# HW2_Schematic.net
KiCad netlist of a schematic drawn in EAGLE
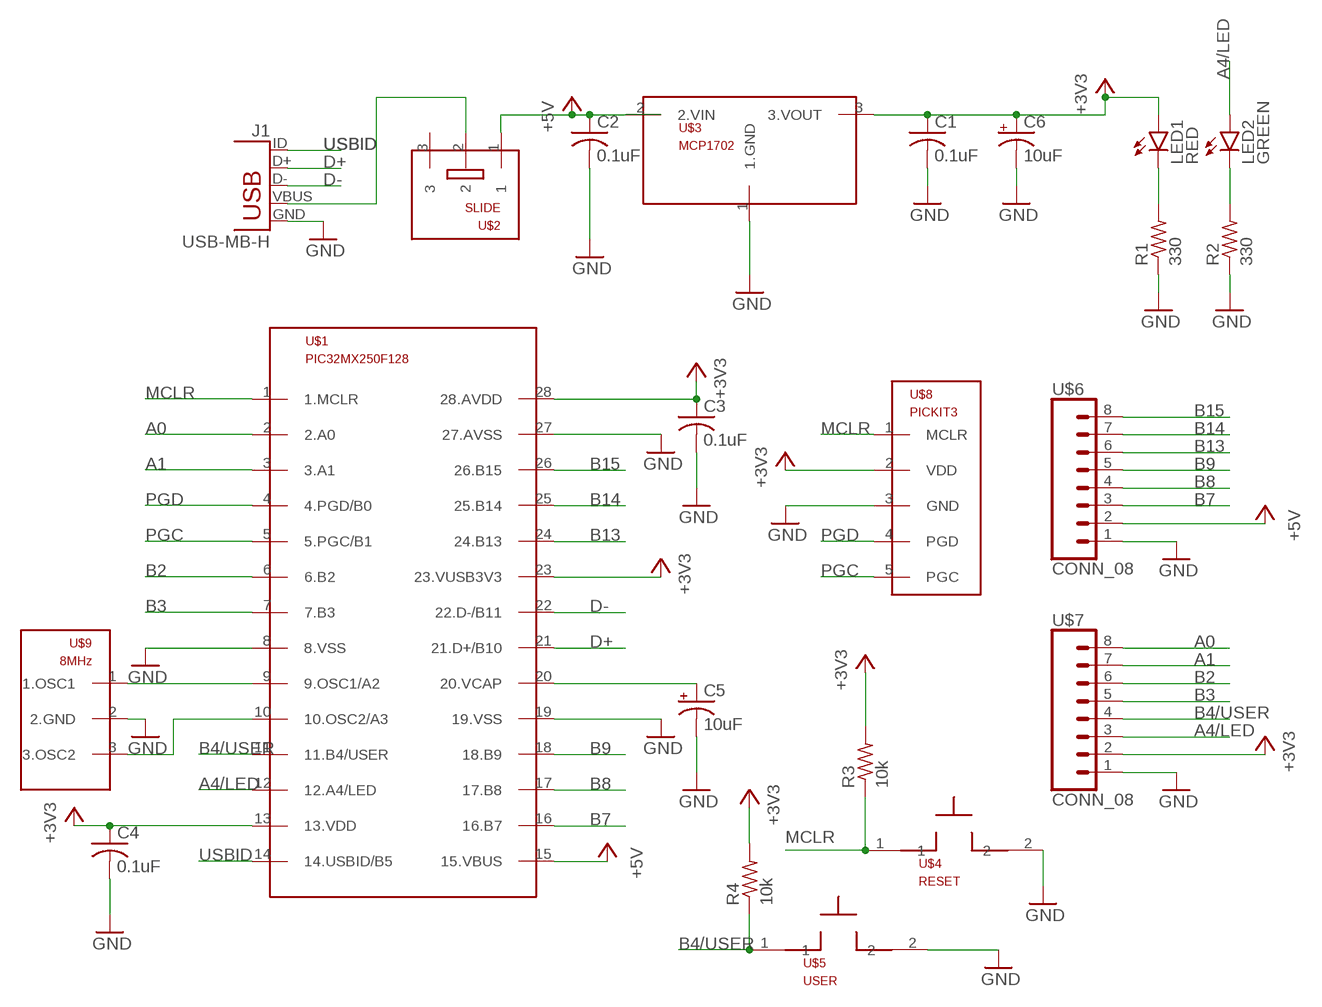
[diagram p0: schematic, sheet 1]

(export (version "E")
  (design (tool "Eeschema 10.0.6"))
  (components
    (comp (ref "C1")
      (value "0.1uF")
      (footprint "eagle-import:C025-025X050")
      (libsource (lib "eagle-import") (part "C-US025-025X050"))
    )
    (comp (ref "C2")
      (value "0.1uF")
      (footprint "eagle-import:C025-025X050")
      (libsource (lib "eagle-import") (part "C-US025-025X050"))
    )
    (comp (ref "C3")
      (value "0.1uF")
      (footprint "eagle-import:C025-025X050")
      (libsource (lib "eagle-import") (part "C-US025-025X050"))
    )
    (comp (ref "C4")
      (value "0.1uF")
      (footprint "eagle-import:C025-025X050")
      (libsource (lib "eagle-import") (part "C-US025-025X050"))
    )
    (comp (ref "C5")
      (value "10uF")
      (footprint "eagle-import:B45181B")
      (libsource (lib "eagle-import") (part "CPOL-USB45181B"))
    )
    (comp (ref "C6")
      (value "10uF")
      (footprint "eagle-import:B45181B")
      (libsource (lib "eagle-import") (part "CPOL-USB45181B"))
    )
    (comp (ref "J1")
      (value "USB-MB-H")
      (footprint "eagle-import:USB-MB-H")
      (libsource (lib "eagle-import") (part "USB-MB-H"))
    )
    (comp (ref "LED1")
      (value "RED")
      (footprint "eagle-import:LED3MM")
      (libsource (lib "eagle-import") (part "LED3MM"))
    )
    (comp (ref "LED2")
      (value "GREEN")
      (footprint "eagle-import:LED3MM")
      (libsource (lib "eagle-import") (part "LED3MM"))
    )
    (comp (ref "R1")
      (value "330")
      (footprint "eagle-import:0207_10")
      (libsource (lib "eagle-import") (part "R-US_0207/10"))
    )
    (comp (ref "R2")
      (value "330")
      (footprint "eagle-import:0207_10")
      (libsource (lib "eagle-import") (part "R-US_0207/10"))
    )
    (comp (ref "R3")
      (value "10k")
      (footprint "eagle-import:0207_10")
      (libsource (lib "eagle-import") (part "R-US_0207/10"))
    )
    (comp (ref "R4")
      (value "10k")
      (footprint "eagle-import:0207_10")
      (libsource (lib "eagle-import") (part "R-US_0207/10"))
    )
    (comp (ref "U$1")
      (value "PIC32MX250F128")
      (footprint "eagle-import:DIL28-3")
      (libsource (lib "eagle-import") (part "PIC32MX250F128"))
    )
    (comp (ref "U$2")
      (value "SLIDE")
      (footprint "eagle-import:SLIDE")
      (libsource (lib "eagle-import") (part "SLIDE"))
    )
    (comp (ref "U$3")
      (value "MCP1702")
      (footprint "eagle-import:TO92")
      (libsource (lib "eagle-import") (part "MCP1702"))
    )
    (comp (ref "U$4")
      (value "RESET")
      (footprint "eagle-import:PB")
      (libsource (lib "eagle-import") (part "PB"))
    )
    (comp (ref "U$5")
      (value "USER")
      (footprint "eagle-import:PB")
      (libsource (lib "eagle-import") (part "PB"))
    )
    (comp (ref "U$6")
      (value "CONN_08")
      (footprint "eagle-import:1X08")
      (libsource (lib "eagle-import") (part "CONN_08"))
    )
    (comp (ref "U$7")
      (value "CONN_08")
      (footprint "eagle-import:1X08")
      (libsource (lib "eagle-import") (part "CONN_08"))
    )
    (comp (ref "U$8")
      (value "PICKIT3")
      (footprint "eagle-import:1X05")
      (libsource (lib "eagle-import") (part "PICKIT3"))
    )
    (comp (ref "U$9")
      (value "8MHz")
      (footprint "eagle-import:OSC")
      (libsource (lib "eagle-import") (part "OSC"))
    )
  )
  (nets
    (net (code "1") (name "+3V3") (class "Default")
      (node (ref "C1") (pin "1") (pinfunction "1_1") (pintype "passive"))
      (node (ref "C3") (pin "1") (pinfunction "1_1") (pintype "passive"))
      (node (ref "C4") (pin "1") (pinfunction "1_1") (pintype "passive"))
      (node (ref "C6") (pin "+") (pinfunction "+_+") (pintype "passive"))
      (node (ref "LED1") (pin "A") (pinfunction "A_A") (pintype "passive"))
      (node (ref "R3") (pin "2") (pinfunction "2_2") (pintype "passive"))
      (node (ref "R4") (pin "2") (pinfunction "2_2") (pintype "passive"))
      (node (ref "U$1") (pin "13") (pinfunction "13.VDD_13") (pintype "bidirectional"))
      (node (ref "U$1") (pin "23") (pinfunction "23.VUSB3V3_23") (pintype "bidirectional"))
      (node (ref "U$1") (pin "28") (pinfunction "28.AVDD_28") (pintype "bidirectional"))
      (node (ref "U$3") (pin "3") (pinfunction "3.VOUT_3") (pintype "bidirectional"))
      (node (ref "U$7") (pin "2") (pinfunction "2_2") (pintype "passive"))
      (node (ref "U$8") (pin "2") (pinfunction "VDD_2") (pintype "bidirectional"))
    )
    (net (code "2") (name "+5V") (class "Default")
      (node (ref "C2") (pin "1") (pinfunction "1_1") (pintype "passive"))
      (node (ref "U$1") (pin "15") (pinfunction "15.VBUS_15") (pintype "bidirectional"))
      (node (ref "U$2") (pin "1") (pinfunction "1_1") (pintype "bidirectional"))
      (node (ref "U$3") (pin "2") (pinfunction "2.VIN_2") (pintype "bidirectional"))
      (node (ref "U$6") (pin "2") (pinfunction "2_2") (pintype "passive"))
    )
    (net (code "3") (name "/A0") (class "Default")
      (node (ref "U$1") (pin "2") (pinfunction "2.A0_2") (pintype "bidirectional"))
      (node (ref "U$7") (pin "8") (pinfunction "8_8") (pintype "passive"))
    )
    (net (code "4") (name "/A1") (class "Default")
      (node (ref "U$1") (pin "3") (pinfunction "3.A1_3") (pintype "bidirectional"))
      (node (ref "U$7") (pin "7") (pinfunction "7_7") (pintype "passive"))
    )
    (net (code "5") (name "/A4{slash}LED") (class "Default")
      (node (ref "LED2") (pin "A") (pinfunction "A_A") (pintype "passive"))
      (node (ref "U$1") (pin "12") (pinfunction "12.A4/LED_12") (pintype "bidirectional"))
      (node (ref "U$7") (pin "3") (pinfunction "3_3") (pintype "passive"))
    )
    (net (code "6") (name "/B2") (class "Default")
      (node (ref "U$1") (pin "6") (pinfunction "6.B2_6") (pintype "bidirectional"))
      (node (ref "U$7") (pin "6") (pinfunction "6_6") (pintype "passive"))
    )
    (net (code "7") (name "/B3") (class "Default")
      (node (ref "U$1") (pin "7") (pinfunction "7.B3_7") (pintype "bidirectional"))
      (node (ref "U$7") (pin "5") (pinfunction "5_5") (pintype "passive"))
    )
    (net (code "8") (name "/B4{slash}USER") (class "Default")
      (node (ref "R4") (pin "1") (pinfunction "1_1") (pintype "passive"))
      (node (ref "U$1") (pin "11") (pinfunction "11.B4/USER_11") (pintype "bidirectional"))
      (node (ref "U$5") (pin "1") (pinfunction "1_1") (pintype "bidirectional"))
      (node (ref "U$7") (pin "4") (pinfunction "4_4") (pintype "passive"))
    )
    (net (code "9") (name "/B7") (class "Default")
      (node (ref "U$1") (pin "16") (pinfunction "16.B7_16") (pintype "bidirectional"))
      (node (ref "U$6") (pin "3") (pinfunction "3_3") (pintype "passive"))
    )
    (net (code "10") (name "/B8") (class "Default")
      (node (ref "U$1") (pin "17") (pinfunction "17.B8_17") (pintype "bidirectional"))
      (node (ref "U$6") (pin "4") (pinfunction "4_4") (pintype "passive"))
    )
    (net (code "11") (name "/B9") (class "Default")
      (node (ref "U$1") (pin "18") (pinfunction "18.B9_18") (pintype "bidirectional"))
      (node (ref "U$6") (pin "5") (pinfunction "5_5") (pintype "passive"))
    )
    (net (code "12") (name "/B13") (class "Default")
      (node (ref "U$1") (pin "24") (pinfunction "24.B13_24") (pintype "bidirectional"))
      (node (ref "U$6") (pin "6") (pinfunction "6_6") (pintype "passive"))
    )
    (net (code "13") (name "/B14") (class "Default")
      (node (ref "U$1") (pin "25") (pinfunction "25.B14_25") (pintype "bidirectional"))
      (node (ref "U$6") (pin "7") (pinfunction "7_7") (pintype "passive"))
    )
    (net (code "14") (name "/B15") (class "Default")
      (node (ref "U$1") (pin "26") (pinfunction "26.B15_26") (pintype "bidirectional"))
      (node (ref "U$6") (pin "8") (pinfunction "8_8") (pintype "passive"))
    )
    (net (code "15") (name "/D+") (class "Default")
      (node (ref "J1") (pin "D+") (pinfunction "D+_D+") (pintype "bidirectional"))
      (node (ref "U$1") (pin "21") (pinfunction "21.D+/B10_21") (pintype "bidirectional"))
    )
    (net (code "16") (name "/D-") (class "Default")
      (node (ref "J1") (pin "D-") (pinfunction "D-_D-") (pintype "bidirectional"))
      (node (ref "U$1") (pin "22") (pinfunction "22.D-/B11_22") (pintype "bidirectional"))
    )
    (net (code "17") (name "/MCLR") (class "Default")
      (node (ref "R3") (pin "1") (pinfunction "1_1") (pintype "passive"))
      (node (ref "U$1") (pin "1") (pinfunction "1.MCLR_1") (pintype "bidirectional"))
      (node (ref "U$4") (pin "1") (pinfunction "1_1") (pintype "bidirectional"))
      (node (ref "U$8") (pin "1") (pinfunction "MCLR_1") (pintype "bidirectional"))
    )
    (net (code "18") (name "/PGC") (class "Default")
      (node (ref "U$1") (pin "5") (pinfunction "5.PGC/B1_5") (pintype "bidirectional"))
      (node (ref "U$8") (pin "5") (pinfunction "PGC_5") (pintype "bidirectional"))
    )
    (net (code "19") (name "/PGD") (class "Default")
      (node (ref "U$1") (pin "4") (pinfunction "4.PGD/B0_4") (pintype "bidirectional"))
      (node (ref "U$8") (pin "4") (pinfunction "PGD_4") (pintype "bidirectional"))
    )
    (net (code "20") (name "/USBID") (class "Default")
      (node (ref "J1") (pin "ID") (pinfunction "ID_ID") (pintype "bidirectional"))
      (node (ref "U$1") (pin "14") (pinfunction "14.USBID/B5_14") (pintype "bidirectional"))
    )
    (net (code "21") (name "GND") (class "Default")
      (node (ref "C1") (pin "2") (pinfunction "2_2") (pintype "passive"))
      (node (ref "C2") (pin "2") (pinfunction "2_2") (pintype "passive"))
      (node (ref "C3") (pin "2") (pinfunction "2_2") (pintype "passive"))
      (node (ref "C4") (pin "2") (pinfunction "2_2") (pintype "passive"))
      (node (ref "C5") (pin "-") (pinfunction "-_-") (pintype "passive"))
      (node (ref "C6") (pin "-") (pinfunction "-_-") (pintype "passive"))
      (node (ref "J1") (pin "GND") (pinfunction "GND_GND") (pintype "bidirectional"))
      (node (ref "R1") (pin "1") (pinfunction "1_1") (pintype "passive"))
      (node (ref "R2") (pin "1") (pinfunction "1_1") (pintype "passive"))
      (node (ref "U$1") (pin "19") (pinfunction "19.VSS_19") (pintype "bidirectional"))
      (node (ref "U$1") (pin "27") (pinfunction "27.AVSS_27") (pintype "bidirectional"))
      (node (ref "U$1") (pin "8") (pinfunction "8.VSS_8") (pintype "bidirectional"))
      (node (ref "U$3") (pin "1") (pinfunction "1.GND_1") (pintype "bidirectional"))
      (node (ref "U$4") (pin "2") (pinfunction "2_2") (pintype "bidirectional"))
      (node (ref "U$5") (pin "2") (pinfunction "2_2") (pintype "bidirectional"))
      (node (ref "U$6") (pin "1") (pinfunction "1_1") (pintype "passive"))
      (node (ref "U$7") (pin "1") (pinfunction "1_1") (pintype "passive"))
      (node (ref "U$8") (pin "3") (pinfunction "GND_3") (pintype "bidirectional"))
      (node (ref "U$9") (pin "2") (pinfunction "2.GND_2") (pintype "bidirectional"))
    )
    (net (code "22") (name "Net-(J1-PadVBUS)") (class "Default")
      (node (ref "J1") (pin "VBUS") (pinfunction "VBUS_VBUS") (pintype "bidirectional"))
      (node (ref "U$2") (pin "2") (pinfunction "2_2") (pintype "bidirectional"))
    )
    (net (code "23") (name "Net-(LED1-C)") (class "Default")
      (node (ref "LED1") (pin "K") (pinfunction "C_K") (pintype "passive"))
      (node (ref "R1") (pin "2") (pinfunction "2_2") (pintype "passive"))
    )
    (net (code "24") (name "Net-(LED2-C)") (class "Default")
      (node (ref "LED2") (pin "K") (pinfunction "C_K") (pintype "passive"))
      (node (ref "R2") (pin "2") (pinfunction "2_2") (pintype "passive"))
    )
    (net (code "25") (name "Net-(U$1-9.OSC1{slash}A2)") (class "Default")
      (node (ref "U$1") (pin "9") (pinfunction "9.OSC1/A2_9") (pintype "bidirectional"))
      (node (ref "U$9") (pin "1") (pinfunction "1.OSC1_1") (pintype "bidirectional"))
    )
    (net (code "26") (name "Net-(U$1-10.OSC2{slash}A3)") (class "Default")
      (node (ref "U$1") (pin "10") (pinfunction "10.OSC2/A3_10") (pintype "bidirectional"))
      (node (ref "U$9") (pin "3") (pinfunction "3.OSC2_3") (pintype "bidirectional"))
    )
    (net (code "27") (name "Net-(U$1-20.VCAP)") (class "Default")
      (node (ref "C5") (pin "+") (pinfunction "+_+") (pintype "passive"))
      (node (ref "U$1") (pin "20") (pinfunction "20.VCAP_20") (pintype "bidirectional"))
    )
    (net (code "28") (name "unconnected-(U$2-Pad3)") (class "Default")
      (node (ref "U$2") (pin "3") (pinfunction "3_3") (pintype "bidirectional"))
    )
  )
)
